# GT_4SBalancer.net
KiCad netlist of a schematic drawn in Altium Designer
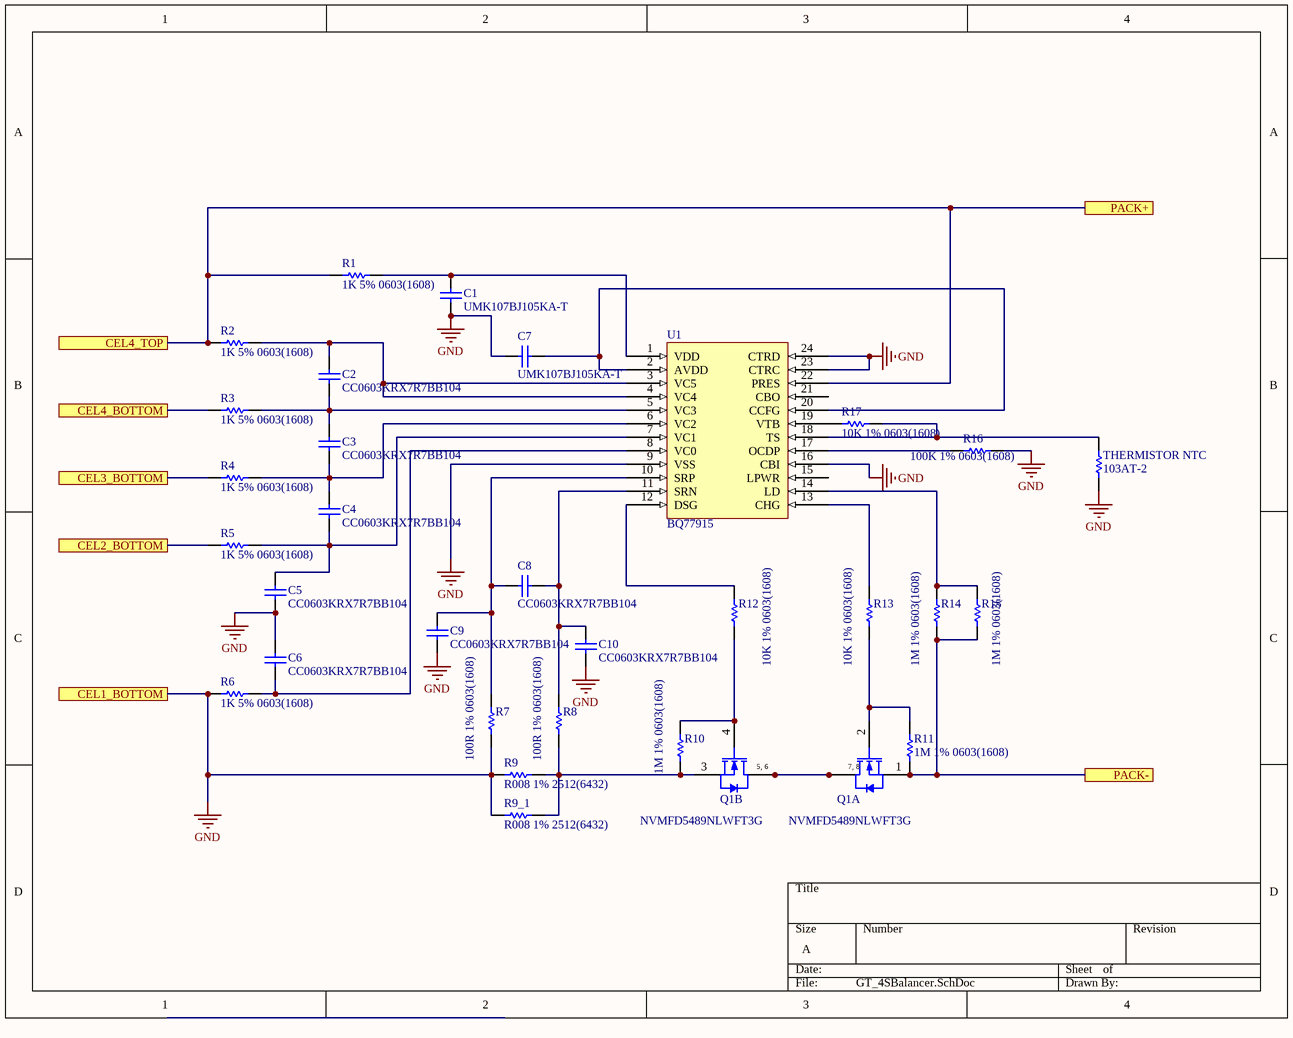
[diagram p0: GT_4SBalancer.SchDoc]

(export (version "E")
  (design (tool "Eeschema 10.0.6"))
  (components
    (comp (ref "C1")
      (value "UMK107BJ105KA-T")
      (footprint "CAPC1608X90X35ML10T25")
      (description "Chip Capacitor, 1 uF, +/- 10%, 50 V, -55 to 85 degC, 0603 (1608 Metric), RoHS, Tape and Reel")
      (fields (field (name "TOLERANCE") "±10%") (field (name "MANUFACTURER") "Taiyo Yuden"))
      (libsource (lib "Altium Content Vault") (part "CAP-NP-2"))
    )
    (comp (ref "C2")
      (value "CC0603KRX7R7BB104")
      (footprint "CAPC1608X90X40ML10T20")
      (fields (field (name "TOLERANCE") "±10%") (field (name "MANUFACTURER") "Yageo"))
      (libsource (lib "Altium Content Vault") (part "CAP-NP-2"))
    )
    (comp (ref "C3")
      (value "CC0603KRX7R7BB104")
      (footprint "CAPC1608X90X40ML10T20")
      (fields (field (name "TOLERANCE") "±10%") (field (name "MANUFACTURER") "Yageo"))
      (libsource (lib "Altium Content Vault") (part "CAP-NP-2"))
    )
    (comp (ref "C4")
      (value "CC0603KRX7R7BB104")
      (footprint "CAPC1608X90X40ML10T20")
      (fields (field (name "TOLERANCE") "±10%") (field (name "MANUFACTURER") "Yageo"))
      (libsource (lib "Altium Content Vault") (part "CAP-NP-2"))
    )
    (comp (ref "C5")
      (value "CC0603KRX7R7BB104")
      (footprint "CAPC1608X90X40ML10T20")
      (fields (field (name "TOLERANCE") "±10%") (field (name "MANUFACTURER") "Yageo"))
      (libsource (lib "Altium Content Vault") (part "CAP-NP-2"))
    )
    (comp (ref "C6")
      (value "CC0603KRX7R7BB104")
      (footprint "CAPC1608X90X40ML10T20")
      (fields (field (name "TOLERANCE") "±10%") (field (name "MANUFACTURER") "Yageo"))
      (libsource (lib "Altium Content Vault") (part "CAP-NP-2"))
    )
    (comp (ref "C7")
      (value "UMK107BJ105KA-T")
      (footprint "CAPC1608X90X35ML10T25")
      (description "Chip Capacitor, 1 uF, +/- 10%, 50 V, -55 to 85 degC, 0603 (1608 Metric), RoHS, Tape and Reel")
      (fields (field (name "TOLERANCE") "±10%") (field (name "MANUFACTURER") "Taiyo Yuden"))
      (libsource (lib "Altium Content Vault") (part "CAP-NP-2"))
    )
    (comp (ref "C8")
      (value "CC0603KRX7R7BB104")
      (footprint "CAPC1608X90X40ML10T20")
      (fields (field (name "TOLERANCE") "±10%") (field (name "MANUFACTURER") "Yageo"))
      (libsource (lib "Altium Content Vault") (part "CAP-NP-2"))
    )
    (comp (ref "C9")
      (value "CC0603KRX7R7BB104")
      (footprint "CAPC1608X90X40ML10T20")
      (fields (field (name "TOLERANCE") "±10%") (field (name "MANUFACTURER") "Yageo"))
      (libsource (lib "Altium Content Vault") (part "CAP-NP-2"))
    )
    (comp (ref "C10")
      (value "CC0603KRX7R7BB104")
      (footprint "CAPC1608X90X40ML10T20")
      (fields (field (name "TOLERANCE") "±10%") (field (name "MANUFACTURER") "Yageo"))
      (libsource (lib "Altium Content Vault") (part "CAP-NP-2"))
    )
    (comp (ref "Q1")
      (value "NVMFD5489NLWFT3G")
      (footprint "ONSC-DFN-8-506BT_V")
      (description "Power MOSFET, 60 V, 12 A, 65 mOhm, Dual N-Channel Logic Level, 8-Pin DFN, Pb-Free, Tape and Reel")
      (fields (field (name "MANUFACTURER") "On Semiconductor"))
      (libsource (lib "Altium Content Vault") (part "ONSC-NNMOS-8_D"))
    )
    (comp (ref "R1")
      (value "1K 5% 0603(1608)")
      (footprint "RESC0603(1608)_L")
      (description "1K 0.1W 5% 0603 (1608 Metric)  SMD")
      (fields (field (name "TOLERANCE") "5 %") (field (name "POWER") "0.1 W"))
      (libsource (lib "Altium Content Vault") (part "RES"))
    )
    (comp (ref "R2")
      (value "1K 5% 0603(1608)")
      (footprint "RESC0603(1608)_L")
      (description "1K 0.1W 5% 0603 (1608 Metric)  SMD")
      (fields (field (name "TOLERANCE") "5 %") (field (name "POWER") "0.1 W"))
      (libsource (lib "Altium Content Vault") (part "RES"))
    )
    (comp (ref "R3")
      (value "1K 5% 0603(1608)")
      (footprint "RESC0603(1608)_L")
      (description "1K 0.1W 5% 0603 (1608 Metric)  SMD")
      (fields (field (name "TOLERANCE") "5 %") (field (name "POWER") "0.1 W"))
      (libsource (lib "Altium Content Vault") (part "RES"))
    )
    (comp (ref "R4")
      (value "1K 5% 0603(1608)")
      (footprint "RESC0603(1608)_L")
      (description "1K 0.1W 5% 0603 (1608 Metric)  SMD")
      (fields (field (name "TOLERANCE") "5 %") (field (name "POWER") "0.1 W"))
      (libsource (lib "Altium Content Vault") (part "RES"))
    )
    (comp (ref "R5")
      (value "1K 5% 0603(1608)")
      (footprint "RESC0603(1608)_L")
      (description "1K 0.1W 5% 0603 (1608 Metric)  SMD")
      (fields (field (name "TOLERANCE") "5 %") (field (name "POWER") "0.1 W"))
      (libsource (lib "Altium Content Vault") (part "RES"))
    )
    (comp (ref "R6")
      (value "1K 5% 0603(1608)")
      (footprint "RESC0603(1608)_L")
      (description "1K 0.1W 5% 0603 (1608 Metric)  SMD")
      (fields (field (name "TOLERANCE") "5 %") (field (name "POWER") "0.1 W"))
      (libsource (lib "Altium Content Vault") (part "RES"))
    )
    (comp (ref "R7")
      (value "100R 1% 0603(1608)")
      (footprint "RESC0603(1608)_M")
      (description "100R 0.1W 1% 0603 (1608 Metric)  SMD")
      (fields (field (name "TOLERANCE") "1 %") (field (name "POWER") "0.1 W"))
      (libsource (lib "Altium Content Vault") (part "RES"))
    )
    (comp (ref "R8")
      (value "100R 1% 0603(1608)")
      (footprint "RESC0603(1608)_M")
      (description "100R 0.1W 1% 0603 (1608 Metric)  SMD")
      (fields (field (name "TOLERANCE") "1 %") (field (name "POWER") "0.1 W"))
      (libsource (lib "Altium Content Vault") (part "RES"))
    )
    (comp (ref "R9")
      (value "R008 1% 2512(6432)")
      (footprint "RESC2512(6432)_L")
      (description "30K1 1W 1% 2512 (6432 Metric)  SMD")
      (fields (field (name "POWER") "1 W") (field (name "TOLERANCE") "1 %"))
      (libsource (lib "Altium Content Vault") (part "RES"))
    )
    (comp (ref "R9_1")
      (value "R008 1% 2512(6432)")
      (footprint "RESC2512(6432)_L")
      (description "30K1 1W 1% 2512 (6432 Metric)  SMD")
      (fields (field (name "POWER") "1 W") (field (name "TOLERANCE") "1 %"))
      (libsource (lib "Altium Content Vault") (part "RES"))
    )
    (comp (ref "R10")
      (value "1M 1% 0603(1608)")
      (footprint "RESC0603(1608)_L")
      (description "1M 0.1W 1% 0603 (1608 Metric)  SMD")
      (fields (field (name "POWER") "0.1 W") (field (name "TOLERANCE") "1 %"))
      (libsource (lib "Altium Content Vault") (part "RES"))
    )
    (comp (ref "R11")
      (value "1M 1% 0603(1608)")
      (footprint "RESC0603(1608)_L")
      (description "1M 0.1W 1% 0603 (1608 Metric)  SMD")
      (fields (field (name "POWER") "0.1 W") (field (name "TOLERANCE") "1 %"))
      (libsource (lib "Altium Content Vault") (part "RES"))
    )
    (comp (ref "R12")
      (value "10K 1% 0603(1608)")
      (footprint "RESC0603(1608)_N")
      (description "10K 0.1W 1% 0603 (1608 Metric)  SMD")
      (fields (field (name "POWER") "0.1 W") (field (name "TOLERANCE") "1 %"))
      (libsource (lib "Altium Content Vault") (part "RES"))
    )
    (comp (ref "R13")
      (value "10K 1% 0603(1608)")
      (footprint "RESC0603(1608)_N")
      (description "10K 0.1W 1% 0603 (1608 Metric)  SMD")
      (fields (field (name "POWER") "0.1 W") (field (name "TOLERANCE") "1 %"))
      (libsource (lib "Altium Content Vault") (part "RES"))
    )
    (comp (ref "R14")
      (value "1M 1% 0603(1608)")
      (footprint "RESC0603(1608)_L")
      (description "1M 0.1W 1% 0603 (1608 Metric)  SMD")
      (fields (field (name "POWER") "0.1 W") (field (name "TOLERANCE") "1 %"))
      (libsource (lib "Altium Content Vault") (part "RES"))
    )
    (comp (ref "R15")
      (value "1M 1% 0603(1608)")
      (footprint "RESC0603(1608)_L")
      (description "1M 0.1W 1% 0603 (1608 Metric)  SMD")
      (fields (field (name "POWER") "0.1 W") (field (name "TOLERANCE") "1 %"))
      (libsource (lib "Altium Content Vault") (part "RES"))
    )
    (comp (ref "R16")
      (value "100K 1% 0603(1608)")
      (footprint "RESC0603(1608)_N")
      (description "100K 0.1W 1% 0603 (1608 Metric)  SMD")
      (fields (field (name "POWER") "0.1 W") (field (name "TOLERANCE") "1 %"))
      (libsource (lib "Altium Content Vault") (part "RES"))
    )
    (comp (ref "R17")
      (value "10K 1% 0603(1608)")
      (footprint "RESC0603(1608)_N")
      (description "10K 0.1W 1% 0603 (1608 Metric)  SMD")
      (fields (field (name "POWER") "0.1 W") (field (name "TOLERANCE") "1 %"))
      (libsource (lib "Altium Content Vault") (part "RES"))
    )
    (comp (ref "THERMISTOR NTC")
      (value "103AT-2")
      (footprint "SEMI-103AT-2_V")
      (description "Precision NTC Thermistor, 10 kOhm, +/- 1%, 10 mW, -50 to 110 degC, 2-Pin THD, RoHS, Bulk")
      (fields (field (name "MANUFACTURER") "Semitec") (field (name "TOLERANCE") "1%"))
      (libsource (lib "Altium Content Vault") (part "RES-THERMAL-2"))
    )
    (comp (ref "U1") (value "BQ77915") (footprint "BQ77915") (libsource (lib "GT_4SCHGR") (part "BQ77915")))
  )
  (nets
    (net (code "1") (name "/CEL2_BOTTOM") (class "Default")
      (node (ref "R5") (pin "1") (pinfunction "1_1") (pintype "passive"))
    )
    (net (code "2") (name "/CEL3_BOTTOM") (class "Default")
      (node (ref "R4") (pin "1") (pinfunction "1_1") (pintype "passive"))
    )
    (net (code "3") (name "/CEL4_BOTTOM") (class "Default")
      (node (ref "R3") (pin "1") (pinfunction "1_1") (pintype "passive"))
    )
    (net (code "4") (name "/CEL4_TOP") (class "Default")
      (node (ref "R1") (pin "1") (pinfunction "1_1") (pintype "passive"))
      (node (ref "R2") (pin "1") (pinfunction "1_1") (pintype "passive"))
      (node (ref "U1") (pin "22") (pinfunction "PRES_22") (pintype "input"))
    )
    (net (code "5") (name "/PACK-") (class "Default")
      (node (ref "Q1") (pin "1") (pinfunction "S1_1") (pintype "passive"))
      (node (ref "R11") (pin "1") (pinfunction "1_1") (pintype "passive"))
      (node (ref "R14") (pin "1") (pinfunction "1_1") (pintype "passive"))
      (node (ref "R15") (pin "1") (pinfunction "1_1") (pintype "passive"))
    )
    (net (code "6") (name "GND") (class "Default")
      (node (ref "C1") (pin "1") (pinfunction "1_1") (pintype "passive"))
      (node (ref "C10") (pin "1") (pinfunction "1_1") (pintype "passive"))
      (node (ref "C5") (pin "1") (pinfunction "1_1") (pintype "passive"))
      (node (ref "C6") (pin "2") (pinfunction "2_2") (pintype "passive"))
      (node (ref "C7") (pin "1") (pinfunction "1_1") (pintype "passive"))
      (node (ref "C9") (pin "1") (pinfunction "1_1") (pintype "passive"))
      (node (ref "R16") (pin "2") (pinfunction "2_2") (pintype "passive"))
      (node (ref "R6") (pin "1") (pinfunction "1_1") (pintype "passive"))
      (node (ref "R7") (pin "1") (pinfunction "1_1") (pintype "passive"))
      (node (ref "R9") (pin "1") (pinfunction "1_1") (pintype "passive"))
      (node (ref "R9_1") (pin "1") (pinfunction "1_1") (pintype "passive"))
      (node (ref "THERMISTOR NTC") (pin "1") (pinfunction "1_1") (pintype "passive"))
      (node (ref "U1") (pin "16") (pinfunction "CBI_16") (pintype "input"))
      (node (ref "U1") (pin "23") (pinfunction "CTRC_23") (pintype "input"))
      (node (ref "U1") (pin "24") (pinfunction "CTRD_24") (pintype "input"))
      (node (ref "U1") (pin "9") (pinfunction "VSS_9") (pintype "input"))
    )
    (net (code "7") (name "Net-(Q1A-D1-Pad7)") (class "Default")
      (node (ref "Q1") (pin "5") (pinfunction "D2_5") (pintype "passive"))
      (node (ref "Q1") (pin "6") (pinfunction "D2_6") (pintype "passive"))
      (node (ref "Q1") (pin "7") (pinfunction "D1_7") (pintype "passive"))
      (node (ref "Q1") (pin "8") (pinfunction "D1_8") (pintype "passive"))
    )
    (net (code "8") (name "Net-(Q1A-G1)") (class "Default")
      (node (ref "Q1") (pin "2") (pinfunction "G1_2") (pintype "passive"))
      (node (ref "R11") (pin "2") (pinfunction "2_2") (pintype "passive"))
      (node (ref "R13") (pin "1") (pinfunction "1_1") (pintype "passive"))
    )
    (net (code "9") (name "Net-(Q1B-G2)") (class "Default")
      (node (ref "Q1") (pin "4") (pinfunction "G2_4") (pintype "passive"))
      (node (ref "R10") (pin "2") (pinfunction "2_2") (pintype "passive"))
      (node (ref "R12") (pin "1") (pinfunction "1_1") (pintype "passive"))
    )
    (net (code "10") (name "Net-(Q1B-S2)") (class "Default")
      (node (ref "Q1") (pin "3") (pinfunction "S2_3") (pintype "passive"))
      (node (ref "R10") (pin "1") (pinfunction "1_1") (pintype "passive"))
      (node (ref "R8") (pin "1") (pinfunction "1_1") (pintype "passive"))
      (node (ref "R9") (pin "2") (pinfunction "2_2") (pintype "passive"))
      (node (ref "R9_1") (pin "2") (pinfunction "2_2") (pintype "passive"))
    )
    (net (code "11") (name "Net-(U1-AVDD)") (class "Default")
      (node (ref "C7") (pin "2") (pinfunction "2_2") (pintype "passive"))
      (node (ref "U1") (pin "2") (pinfunction "AVDD_2") (pintype "input"))
      (node (ref "U1") (pin "20") (pinfunction "CCFG_20") (pintype "input"))
    )
    (net (code "12") (name "Net-(U1-CHG)") (class "Default")
      (node (ref "R13") (pin "2") (pinfunction "2_2") (pintype "passive"))
      (node (ref "U1") (pin "13") (pinfunction "CHG_13") (pintype "input"))
    )
    (net (code "13") (name "Net-(U1-DSG)") (class "Default")
      (node (ref "R12") (pin "2") (pinfunction "2_2") (pintype "passive"))
      (node (ref "U1") (pin "12") (pinfunction "DSG_12") (pintype "input"))
    )
    (net (code "14") (name "Net-(U1-LD)") (class "Default")
      (node (ref "R14") (pin "2") (pinfunction "2_2") (pintype "passive"))
      (node (ref "R15") (pin "2") (pinfunction "2_2") (pintype "passive"))
      (node (ref "U1") (pin "14") (pinfunction "LD_14") (pintype "input"))
    )
    (net (code "15") (name "Net-(U1-OCDP)") (class "Default")
      (node (ref "R16") (pin "1") (pinfunction "1_1") (pintype "passive"))
      (node (ref "U1") (pin "17") (pinfunction "OCDP_17") (pintype "input"))
    )
    (net (code "16") (name "Net-(U1-SRN)") (class "Default")
      (node (ref "C10") (pin "2") (pinfunction "2_2") (pintype "passive"))
      (node (ref "C8") (pin "1") (pinfunction "1_1") (pintype "passive"))
      (node (ref "R8") (pin "2") (pinfunction "2_2") (pintype "passive"))
      (node (ref "U1") (pin "11") (pinfunction "SRN_11") (pintype "input"))
    )
    (net (code "17") (name "Net-(U1-SRP)") (class "Default")
      (node (ref "C8") (pin "2") (pinfunction "2_2") (pintype "passive"))
      (node (ref "C9") (pin "2") (pinfunction "2_2") (pintype "passive"))
      (node (ref "R7") (pin "2") (pinfunction "2_2") (pintype "passive"))
      (node (ref "U1") (pin "10") (pinfunction "SRP_10") (pintype "input"))
    )
    (net (code "18") (name "Net-(U1-TS)") (class "Default")
      (node (ref "R17") (pin "1") (pinfunction "1_1") (pintype "passive"))
      (node (ref "THERMISTOR NTC") (pin "2") (pinfunction "2_2") (pintype "passive"))
      (node (ref "U1") (pin "18") (pinfunction "TS_18") (pintype "input"))
    )
    (net (code "19") (name "Net-(U1-VC0)") (class "Default")
      (node (ref "C6") (pin "1") (pinfunction "1_1") (pintype "passive"))
      (node (ref "R6") (pin "2") (pinfunction "2_2") (pintype "passive"))
      (node (ref "U1") (pin "8") (pinfunction "VC0_8") (pintype "input"))
    )
    (net (code "20") (name "Net-(U1-VC1)") (class "Default")
      (node (ref "C4") (pin "1") (pinfunction "1_1") (pintype "passive"))
      (node (ref "C5") (pin "2") (pinfunction "2_2") (pintype "passive"))
      (node (ref "R5") (pin "2") (pinfunction "2_2") (pintype "passive"))
      (node (ref "U1") (pin "7") (pinfunction "VC1_7") (pintype "input"))
    )
    (net (code "21") (name "Net-(U1-VC2)") (class "Default")
      (node (ref "C3") (pin "1") (pinfunction "1_1") (pintype "passive"))
      (node (ref "C4") (pin "2") (pinfunction "2_2") (pintype "passive"))
      (node (ref "R4") (pin "2") (pinfunction "2_2") (pintype "passive"))
      (node (ref "U1") (pin "6") (pinfunction "VC2_6") (pintype "input"))
    )
    (net (code "22") (name "Net-(U1-VC3)") (class "Default")
      (node (ref "C2") (pin "1") (pinfunction "1_1") (pintype "passive"))
      (node (ref "C3") (pin "2") (pinfunction "2_2") (pintype "passive"))
      (node (ref "R3") (pin "2") (pinfunction "2_2") (pintype "passive"))
      (node (ref "U1") (pin "5") (pinfunction "VC3_5") (pintype "input"))
    )
    (net (code "23") (name "Net-(U1-VC4)") (class "Default")
      (node (ref "C2") (pin "2") (pinfunction "2_2") (pintype "passive"))
      (node (ref "R2") (pin "2") (pinfunction "2_2") (pintype "passive"))
      (node (ref "U1") (pin "3") (pinfunction "VC5_3") (pintype "input"))
      (node (ref "U1") (pin "4") (pinfunction "VC4_4") (pintype "input"))
    )
    (net (code "24") (name "Net-(U1-VDD)") (class "Default")
      (node (ref "C1") (pin "2") (pinfunction "2_2") (pintype "passive"))
      (node (ref "R1") (pin "2") (pinfunction "2_2") (pintype "passive"))
      (node (ref "U1") (pin "1") (pinfunction "VDD_1") (pintype "input"))
    )
    (net (code "25") (name "Net-(U1-VTB)") (class "Default")
      (node (ref "R17") (pin "2") (pinfunction "2_2") (pintype "passive"))
      (node (ref "U1") (pin "19") (pinfunction "VTB_19") (pintype "input"))
    )
    (net (code "26") (name "unconnected-(U1-CBO-Pad21)") (class "Default")
      (node (ref "U1") (pin "21") (pinfunction "CBO_21") (pintype "input"))
    )
    (net (code "27") (name "unconnected-(U1-LPWR-Pad15)") (class "Default")
      (node (ref "U1") (pin "15") (pinfunction "LPWR_15") (pintype "input"))
    )
  )
)
